# Ambient_Light_Sensor.net
KiCad netlist of a schematic drawn in EAGLE
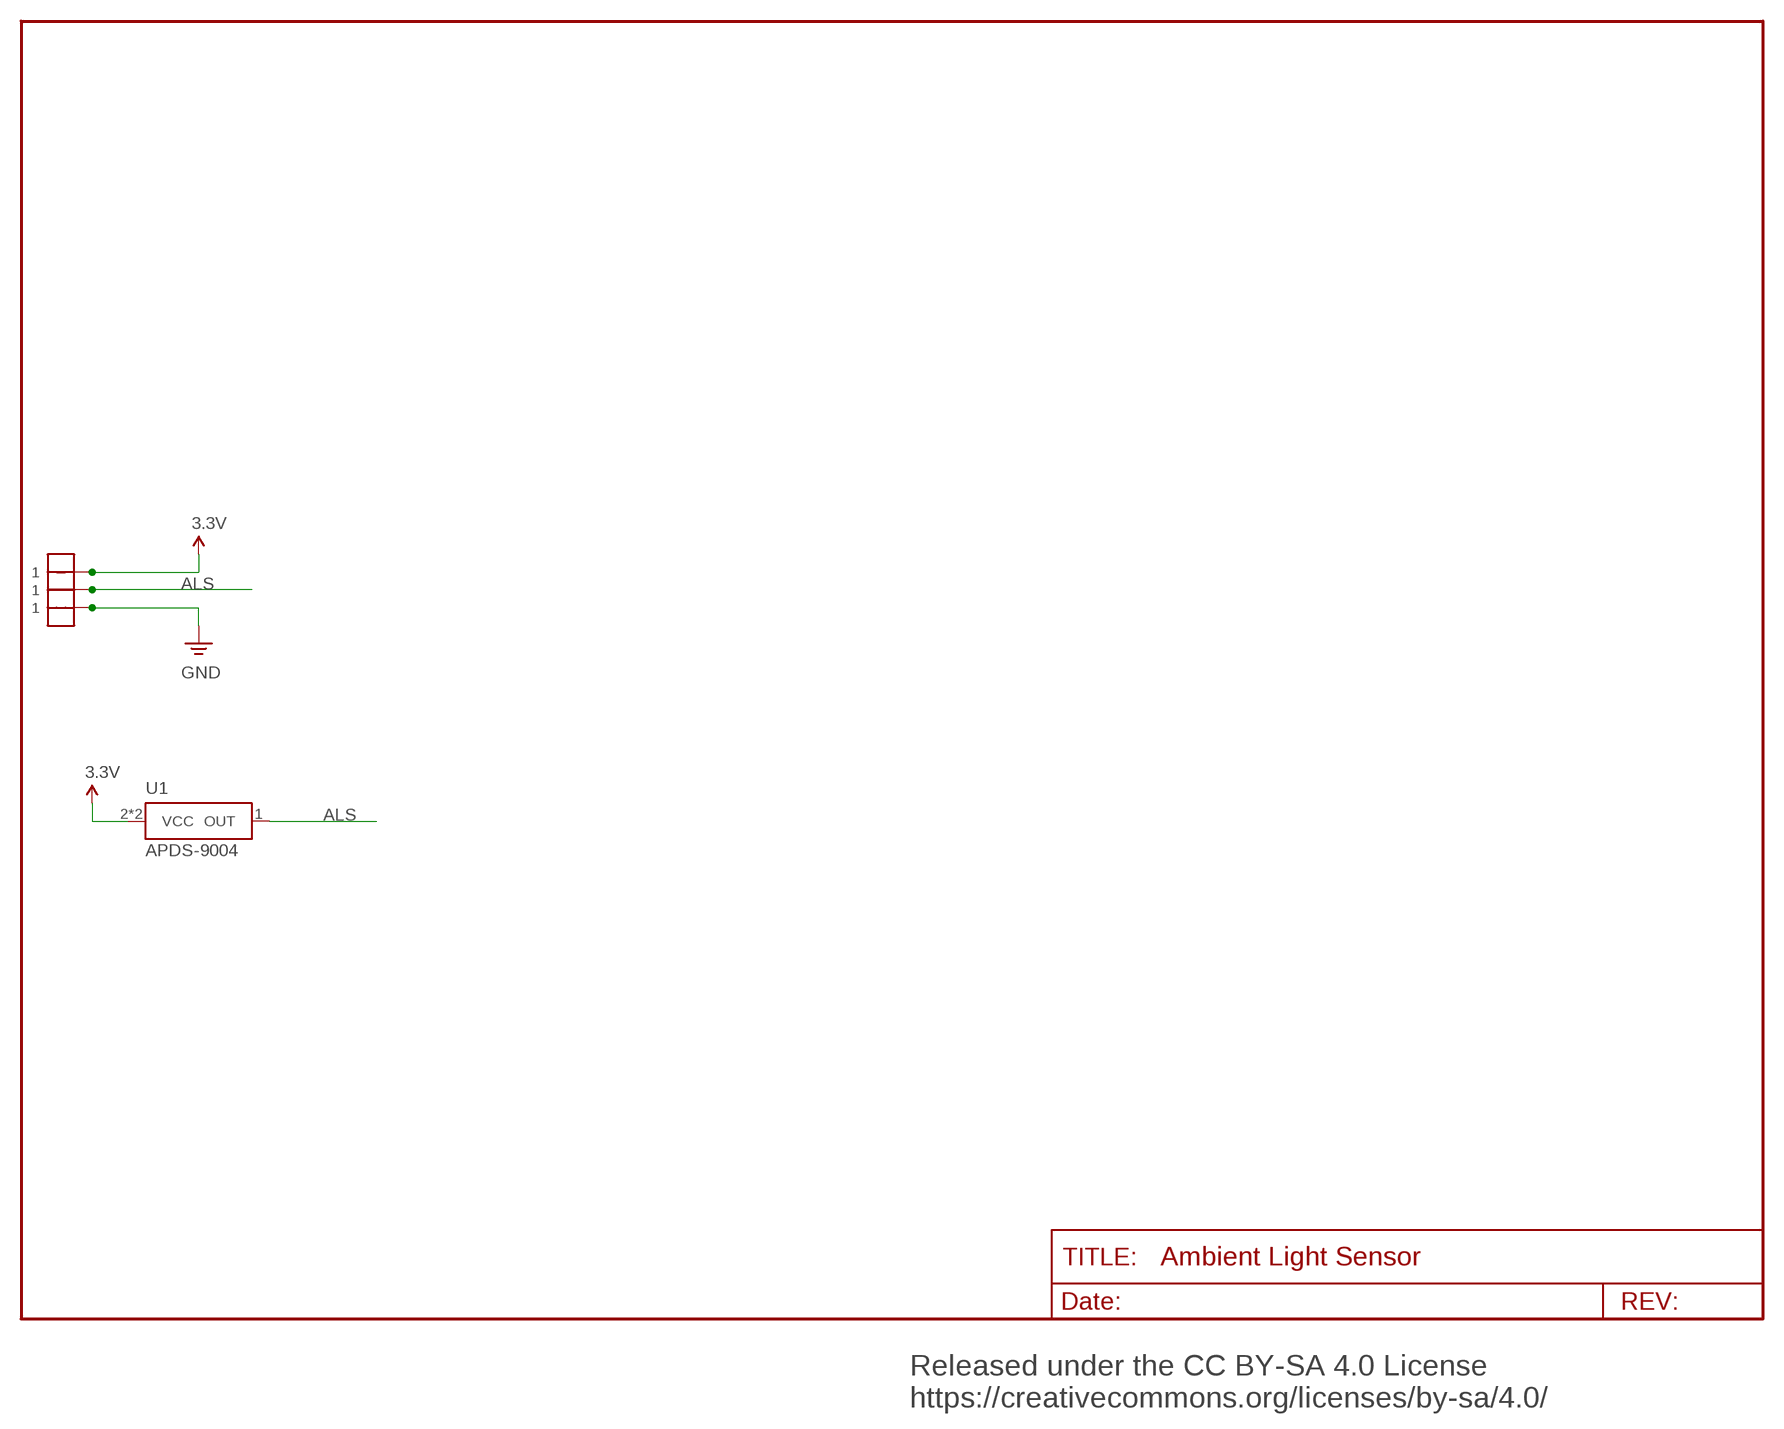
[diagram p0: schematic, sheet 1]

(export (version "E")
  (design (tool "Eeschema 10.0.6"))
  (components
    (comp (ref "U$2")
      (value "S01-4MM")
      (footprint "eagle-import:S01-4MM")
      (libsource (lib "eagle-import") (part "S01-4MM"))
    )
    (comp (ref "U$3")
      (value "S01-4MM")
      (footprint "eagle-import:S01-4MM")
      (libsource (lib "eagle-import") (part "S01-4MM"))
    )
    (comp (ref "U$4")
      (value "S01-4MM")
      (footprint "eagle-import:S01-4MM")
      (libsource (lib "eagle-import") (part "S01-4MM"))
    )
    (comp (ref "U1")
      (value "ADPS-9004")
      (footprint "eagle-import:APDS-9004")
      (libsource (lib "eagle-import") (part "ADPS-9004"))
    )
  )
  (nets
    (net (code "1") (name "/ALS") (class "Default")
      (node (ref "U$3") (pin "P$1") (pinfunction "1_P$1") (pintype "bidirectional"))
      (node (ref "U1") (pin "1") (pinfunction "OUT_1") (pintype "bidirectional"))
    )
    (net (code "2") (name "3.3V") (class "Default")
      (node (ref "U$2") (pin "P$1") (pinfunction "1_P$1") (pintype "bidirectional"))
      (node (ref "U1") (pin "2") (pinfunction "VCC_2") (pintype "bidirectional"))
      (node (ref "U1") (pin "3") (pinfunction "VCC_3") (pintype "bidirectional"))
    )
    (net (code "3") (name "GND") (class "Default")
      (node (ref "U$4") (pin "P$1") (pinfunction "1_P$1") (pintype "bidirectional"))
    )
  )
)
